# JTAG_Trace.net
KiCad netlist of a schematic drawn in Altium Designer
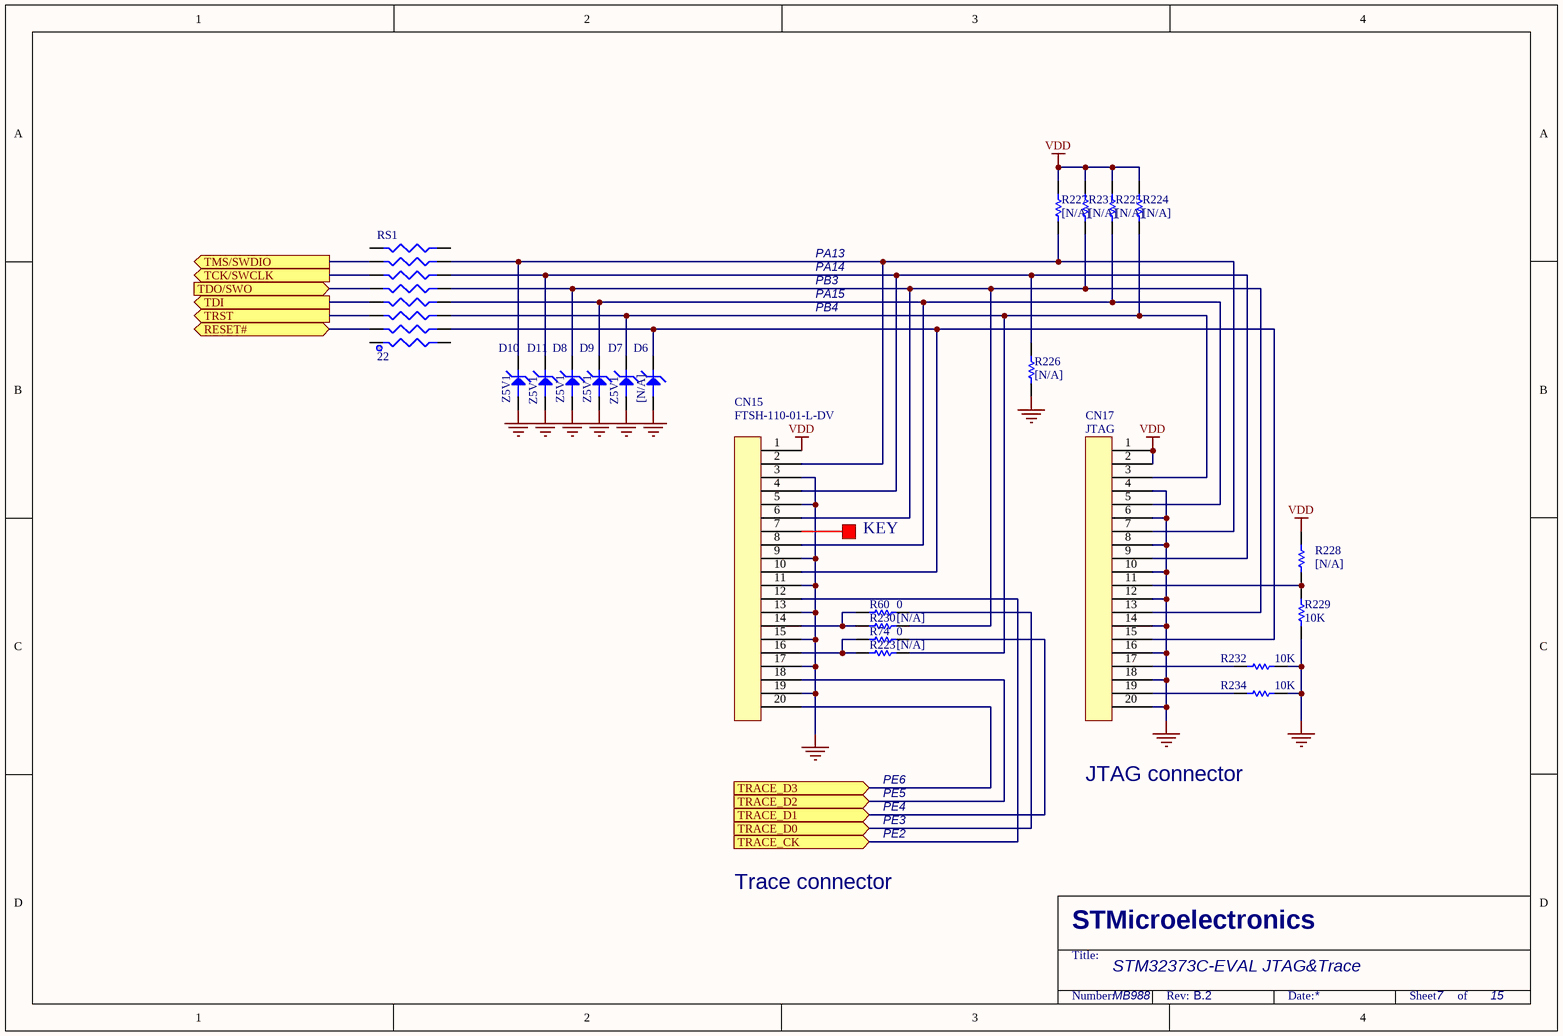
[diagram p0: JTAG&Trace.SchDoc]

(export (version "E")
  (design (tool "Eeschema 10.0.6"))
  (components
    (comp (ref "CN15")
      (value "FTSH-110-01-L-DV")
      (footprint "FTSH-110-01-L-DV")
      (libsource (lib "*") (part "20PIN1"))
    )
    (comp (ref "CN17") (value "JTAG") (footprint "IDC20S") (libsource (lib "*") (part "20PIN1")))
    (comp (ref "D6") (value "[N/A]") (footprint "SOT-23") (libsource (lib "*") (part "BATS5V6")))
    (comp (ref "D7") (value "Z5V1") (footprint "SOT-23") (libsource (lib "*") (part "BATS5V6")))
    (comp (ref "D8") (value "Z5V1") (footprint "SOT-23") (libsource (lib "*") (part "BATS5V6")))
    (comp (ref "D9") (value "Z5V1") (footprint "SOT-23") (libsource (lib "*") (part "BATS5V6")))
    (comp (ref "D10") (value "Z5V1") (footprint "SOT-23") (libsource (lib "*") (part "BATS5V6")))
    (comp (ref "D11") (value "Z5V1") (footprint "SOT-23") (libsource (lib "*") (part "BATS5V6")))
    (comp (ref "R60")
      (value "0")
      (footprint "0603R")
      (description "Resistor")
      (fields (field (name "PUBLISHER") "Altium Limited"))
      (libsource (lib "Miscellaneous Devices") (part "Res1"))
    )
    (comp (ref "R74")
      (value "0")
      (footprint "0603R")
      (description "Resistor")
      (fields (field (name "PUBLISHER") "Altium Limited"))
      (libsource (lib "Miscellaneous Devices") (part "Res1"))
    )
    (comp (ref "R223")
      (value "[N/A]")
      (footprint "0603R")
      (description "Resistor")
      (fields (field (name "PUBLISHER") "Altium Limited"))
      (libsource (lib "Miscellaneous Devices") (part "Res1"))
    )
    (comp (ref "R224")
      (value "[N/A]")
      (footprint "0603R")
      (description "Resistor")
      (fields (field (name "PUBLISHER") "Altium Limited"))
      (libsource (lib "Miscellaneous Devices") (part "Res1"))
    )
    (comp (ref "R225")
      (value "[N/A]")
      (footprint "0603R")
      (description "Resistor")
      (fields (field (name "PUBLISHER") "Altium Limited"))
      (libsource (lib "Miscellaneous Devices") (part "Res1"))
    )
    (comp (ref "R226")
      (value "[N/A]")
      (footprint "0603R")
      (description "Resistor")
      (fields (field (name "PUBLISHER") "Altium Limited"))
      (libsource (lib "Miscellaneous Devices") (part "Res1"))
    )
    (comp (ref "R227")
      (value "[N/A]")
      (footprint "0603R")
      (description "Resistor")
      (fields (field (name "PUBLISHER") "Altium Limited"))
      (libsource (lib "Miscellaneous Devices") (part "Res1"))
    )
    (comp (ref "R228")
      (value "[N/A]")
      (footprint "0603R")
      (description "Resistor")
      (fields (field (name "PUBLISHER") "Altium Limited"))
      (libsource (lib "Miscellaneous Devices") (part "Res1"))
    )
    (comp (ref "R229")
      (value "10K")
      (footprint "0603R")
      (description "Resistor")
      (fields (field (name "PUBLISHER") "Altium Limited"))
      (libsource (lib "Miscellaneous Devices") (part "Res1"))
    )
    (comp (ref "R230")
      (value "[N/A]")
      (footprint "0603R")
      (description "Resistor")
      (fields (field (name "PUBLISHER") "Altium Limited"))
      (libsource (lib "Miscellaneous Devices") (part "Res1"))
    )
    (comp (ref "R231")
      (value "[N/A]")
      (footprint "0603R")
      (description "Resistor")
      (fields (field (name "PUBLISHER") "Altium Limited"))
      (libsource (lib "Miscellaneous Devices") (part "Res1"))
    )
    (comp (ref "R232")
      (value "10K")
      (footprint "0603R")
      (description "Resistor")
      (fields (field (name "PUBLISHER") "Altium Limited"))
      (libsource (lib "Miscellaneous Devices") (part "Res1"))
    )
    (comp (ref "R234")
      (value "10K")
      (footprint "0603R")
      (description "Resistor")
      (fields (field (name "PUBLISHER") "Altium Limited"))
      (libsource (lib "Miscellaneous Devices") (part "Res1"))
    )
    (comp (ref "RS1") (value "22") (footprint "RES8B_0402") (libsource (lib "*") (part "RES8B")))
  )
  (nets
    (net (code "1") (name "/RESET#") (class "Default") (node (ref "RS1") (pin "3") (pintype "passive")))
    (net (code "2") (name "/TCK{slash}SWCLK") (class "Default")
      (node (ref "RS1") (pin "11") (pintype "passive"))
    )
    (net (code "3") (name "/TDI") (class "Default") (node (ref "RS1") (pin "7") (pintype "passive")))
    (net (code "4") (name "/TDO{slash}SWO") (class "Default")
      (node (ref "RS1") (pin "9") (pintype "passive"))
    )
    (net (code "5") (name "/TMS{slash}SWDIO") (class "Default")
      (node (ref "RS1") (pin "13") (pintype "passive"))
    )
    (net (code "6") (name "/TRACE_CK") (class "Default") (node (ref "CN15") (pin "12") (pintype "passive")))
    (net (code "7") (name "/TRACE_D0") (class "Default")
      (node (ref "R60") (pin "2") (pinfunction "2_2") (pintype "passive"))
    )
    (net (code "8") (name "/TRACE_D1") (class "Default")
      (node (ref "R74") (pin "2") (pinfunction "2_2") (pintype "passive"))
    )
    (net (code "9") (name "/TRACE_D2") (class "Default") (node (ref "CN15") (pin "18") (pintype "passive")))
    (net (code "10") (name "/TRACE_D3") (class "Default") (node (ref "CN15") (pin "20") (pintype "passive")))
    (net (code "11") (name "/TRST") (class "Default") (node (ref "RS1") (pin "5") (pintype "passive")))
    (net (code "12") (name "GND") (class "Default")
      (node (ref "CN15") (pin "11") (pintype "passive"))
      (node (ref "CN15") (pin "13") (pintype "passive"))
      (node (ref "CN15") (pin "15") (pintype "passive"))
      (node (ref "CN15") (pin "17") (pintype "passive"))
      (node (ref "CN15") (pin "19") (pintype "passive"))
      (node (ref "CN15") (pin "3") (pintype "passive"))
      (node (ref "CN15") (pin "5") (pintype "passive"))
      (node (ref "CN15") (pin "9") (pintype "passive"))
      (node (ref "CN17") (pin "10") (pintype "passive"))
      (node (ref "CN17") (pin "12") (pintype "passive"))
      (node (ref "CN17") (pin "14") (pintype "passive"))
      (node (ref "CN17") (pin "16") (pintype "passive"))
      (node (ref "CN17") (pin "18") (pintype "passive"))
      (node (ref "CN17") (pin "20") (pintype "passive"))
      (node (ref "CN17") (pin "4") (pintype "passive"))
      (node (ref "CN17") (pin "6") (pintype "passive"))
      (node (ref "CN17") (pin "8") (pintype "passive"))
      (node (ref "D10") (pin "2") (pintype "passive"))
      (node (ref "D11") (pin "2") (pintype "passive"))
      (node (ref "D6") (pin "2") (pintype "passive"))
      (node (ref "D7") (pin "2") (pintype "passive"))
      (node (ref "D8") (pin "2") (pintype "passive"))
      (node (ref "D9") (pin "2") (pintype "passive"))
      (node (ref "R226") (pin "1") (pinfunction "1_1") (pintype "passive"))
      (node (ref "R229") (pin "1") (pinfunction "1_1") (pintype "passive"))
      (node (ref "R232") (pin "1") (pinfunction "1_1") (pintype "passive"))
      (node (ref "R234") (pin "1") (pinfunction "1_1") (pintype "passive"))
    )
    (net (code "13") (name "Net-(CN15-Pad2)") (class "Default")
      (node (ref "CN15") (pin "2") (pintype "passive"))
      (node (ref "CN17") (pin "7") (pintype "passive"))
      (node (ref "D10") (pin "3") (pintype "passive"))
      (node (ref "R227") (pin "1") (pinfunction "1_1") (pintype "passive"))
      (node (ref "RS1") (pin "14") (pintype "passive"))
    )
    (net (code "14") (name "Net-(CN15-Pad4)") (class "Default")
      (node (ref "CN15") (pin "4") (pintype "passive"))
      (node (ref "CN17") (pin "9") (pintype "passive"))
      (node (ref "D11") (pin "3") (pintype "passive"))
      (node (ref "R226") (pin "2") (pinfunction "2_2") (pintype "passive"))
      (node (ref "RS1") (pin "12") (pintype "passive"))
    )
    (net (code "15") (name "Net-(CN15-Pad6)") (class "Default")
      (node (ref "CN15") (pin "6") (pintype "passive"))
      (node (ref "CN17") (pin "13") (pintype "passive"))
      (node (ref "D8") (pin "3") (pintype "passive"))
      (node (ref "R230") (pin "2") (pinfunction "2_2") (pintype "passive"))
      (node (ref "R231") (pin "1") (pinfunction "1_1") (pintype "passive"))
      (node (ref "RS1") (pin "10") (pintype "passive"))
    )
    (net (code "16") (name "Net-(CN15-Pad8)") (class "Default")
      (node (ref "CN15") (pin "8") (pintype "passive"))
      (node (ref "CN17") (pin "5") (pintype "passive"))
      (node (ref "D9") (pin "3") (pintype "passive"))
      (node (ref "R225") (pin "1") (pinfunction "1_1") (pintype "passive"))
      (node (ref "RS1") (pin "8") (pintype "passive"))
    )
    (net (code "17") (name "Net-(CN15-Pad10)") (class "Default")
      (node (ref "CN15") (pin "10") (pintype "passive"))
      (node (ref "CN17") (pin "15") (pintype "passive"))
      (node (ref "D6") (pin "3") (pintype "passive"))
      (node (ref "RS1") (pin "4") (pintype "passive"))
    )
    (net (code "18") (name "Net-(CN15-Pad14)") (class "Default")
      (node (ref "CN15") (pin "14") (pintype "passive"))
      (node (ref "R230") (pin "1") (pinfunction "1_1") (pintype "passive"))
      (node (ref "R60") (pin "1") (pinfunction "1_1") (pintype "passive"))
    )
    (net (code "19") (name "Net-(CN15-Pad16)") (class "Default")
      (node (ref "CN15") (pin "16") (pintype "passive"))
      (node (ref "R223") (pin "1") (pinfunction "1_1") (pintype "passive"))
      (node (ref "R74") (pin "1") (pinfunction "1_1") (pintype "passive"))
    )
    (net (code "20") (name "Net-(CN17-Pad3)") (class "Default")
      (node (ref "CN17") (pin "3") (pintype "passive"))
      (node (ref "D7") (pin "3") (pintype "passive"))
      (node (ref "R223") (pin "2") (pinfunction "2_2") (pintype "passive"))
      (node (ref "R224") (pin "1") (pinfunction "1_1") (pintype "passive"))
      (node (ref "RS1") (pin "6") (pintype "passive"))
    )
    (net (code "21") (name "Net-(CN17-Pad11)") (class "Default")
      (node (ref "CN17") (pin "11") (pintype "passive"))
      (node (ref "R228") (pin "1") (pinfunction "1_1") (pintype "passive"))
      (node (ref "R229") (pin "2") (pinfunction "2_2") (pintype "passive"))
    )
    (net (code "22") (name "Net-(CN17-Pad17)") (class "Default")
      (node (ref "CN17") (pin "17") (pintype "passive"))
      (node (ref "R232") (pin "2") (pinfunction "2_2") (pintype "passive"))
    )
    (net (code "23") (name "Net-(CN17-Pad19)") (class "Default")
      (node (ref "CN17") (pin "19") (pintype "passive"))
      (node (ref "R234") (pin "2") (pinfunction "2_2") (pintype "passive"))
    )
    (net (code "24") (name "VDD") (class "Default")
      (node (ref "CN15") (pin "1") (pintype "passive"))
      (node (ref "CN17") (pin "1") (pintype "passive"))
      (node (ref "CN17") (pin "2") (pintype "passive"))
      (node (ref "R224") (pin "2") (pinfunction "2_2") (pintype "passive"))
      (node (ref "R225") (pin "2") (pinfunction "2_2") (pintype "passive"))
      (node (ref "R227") (pin "2") (pinfunction "2_2") (pintype "passive"))
      (node (ref "R228") (pin "2") (pinfunction "2_2") (pintype "passive"))
      (node (ref "R231") (pin "2") (pinfunction "2_2") (pintype "passive"))
    )
    (net (code "25") (name "unconnected-(CN15-Pad7)") (class "Default")
      (node (ref "CN15") (pin "7") (pintype "passive"))
    )
    (net (code "26") (name "unconnected-(RS1-Pad1)") (class "Default")
      (node (ref "RS1") (pin "1") (pintype "passive"))
    )
    (net (code "27") (name "unconnected-(RS1-Pad2)") (class "Default")
      (node (ref "RS1") (pin "2") (pintype "passive"))
    )
    (net (code "28") (name "unconnected-(RS1-Pad15)") (class "Default")
      (node (ref "RS1") (pin "15") (pintype "passive"))
    )
    (net (code "29") (name "unconnected-(RS1-Pad16)") (class "Default")
      (node (ref "RS1") (pin "16") (pintype "passive"))
    )
  )
)
